# Fri3D_2020_Power.net
KiCad netlist of a schematic drawn in Altium Designer
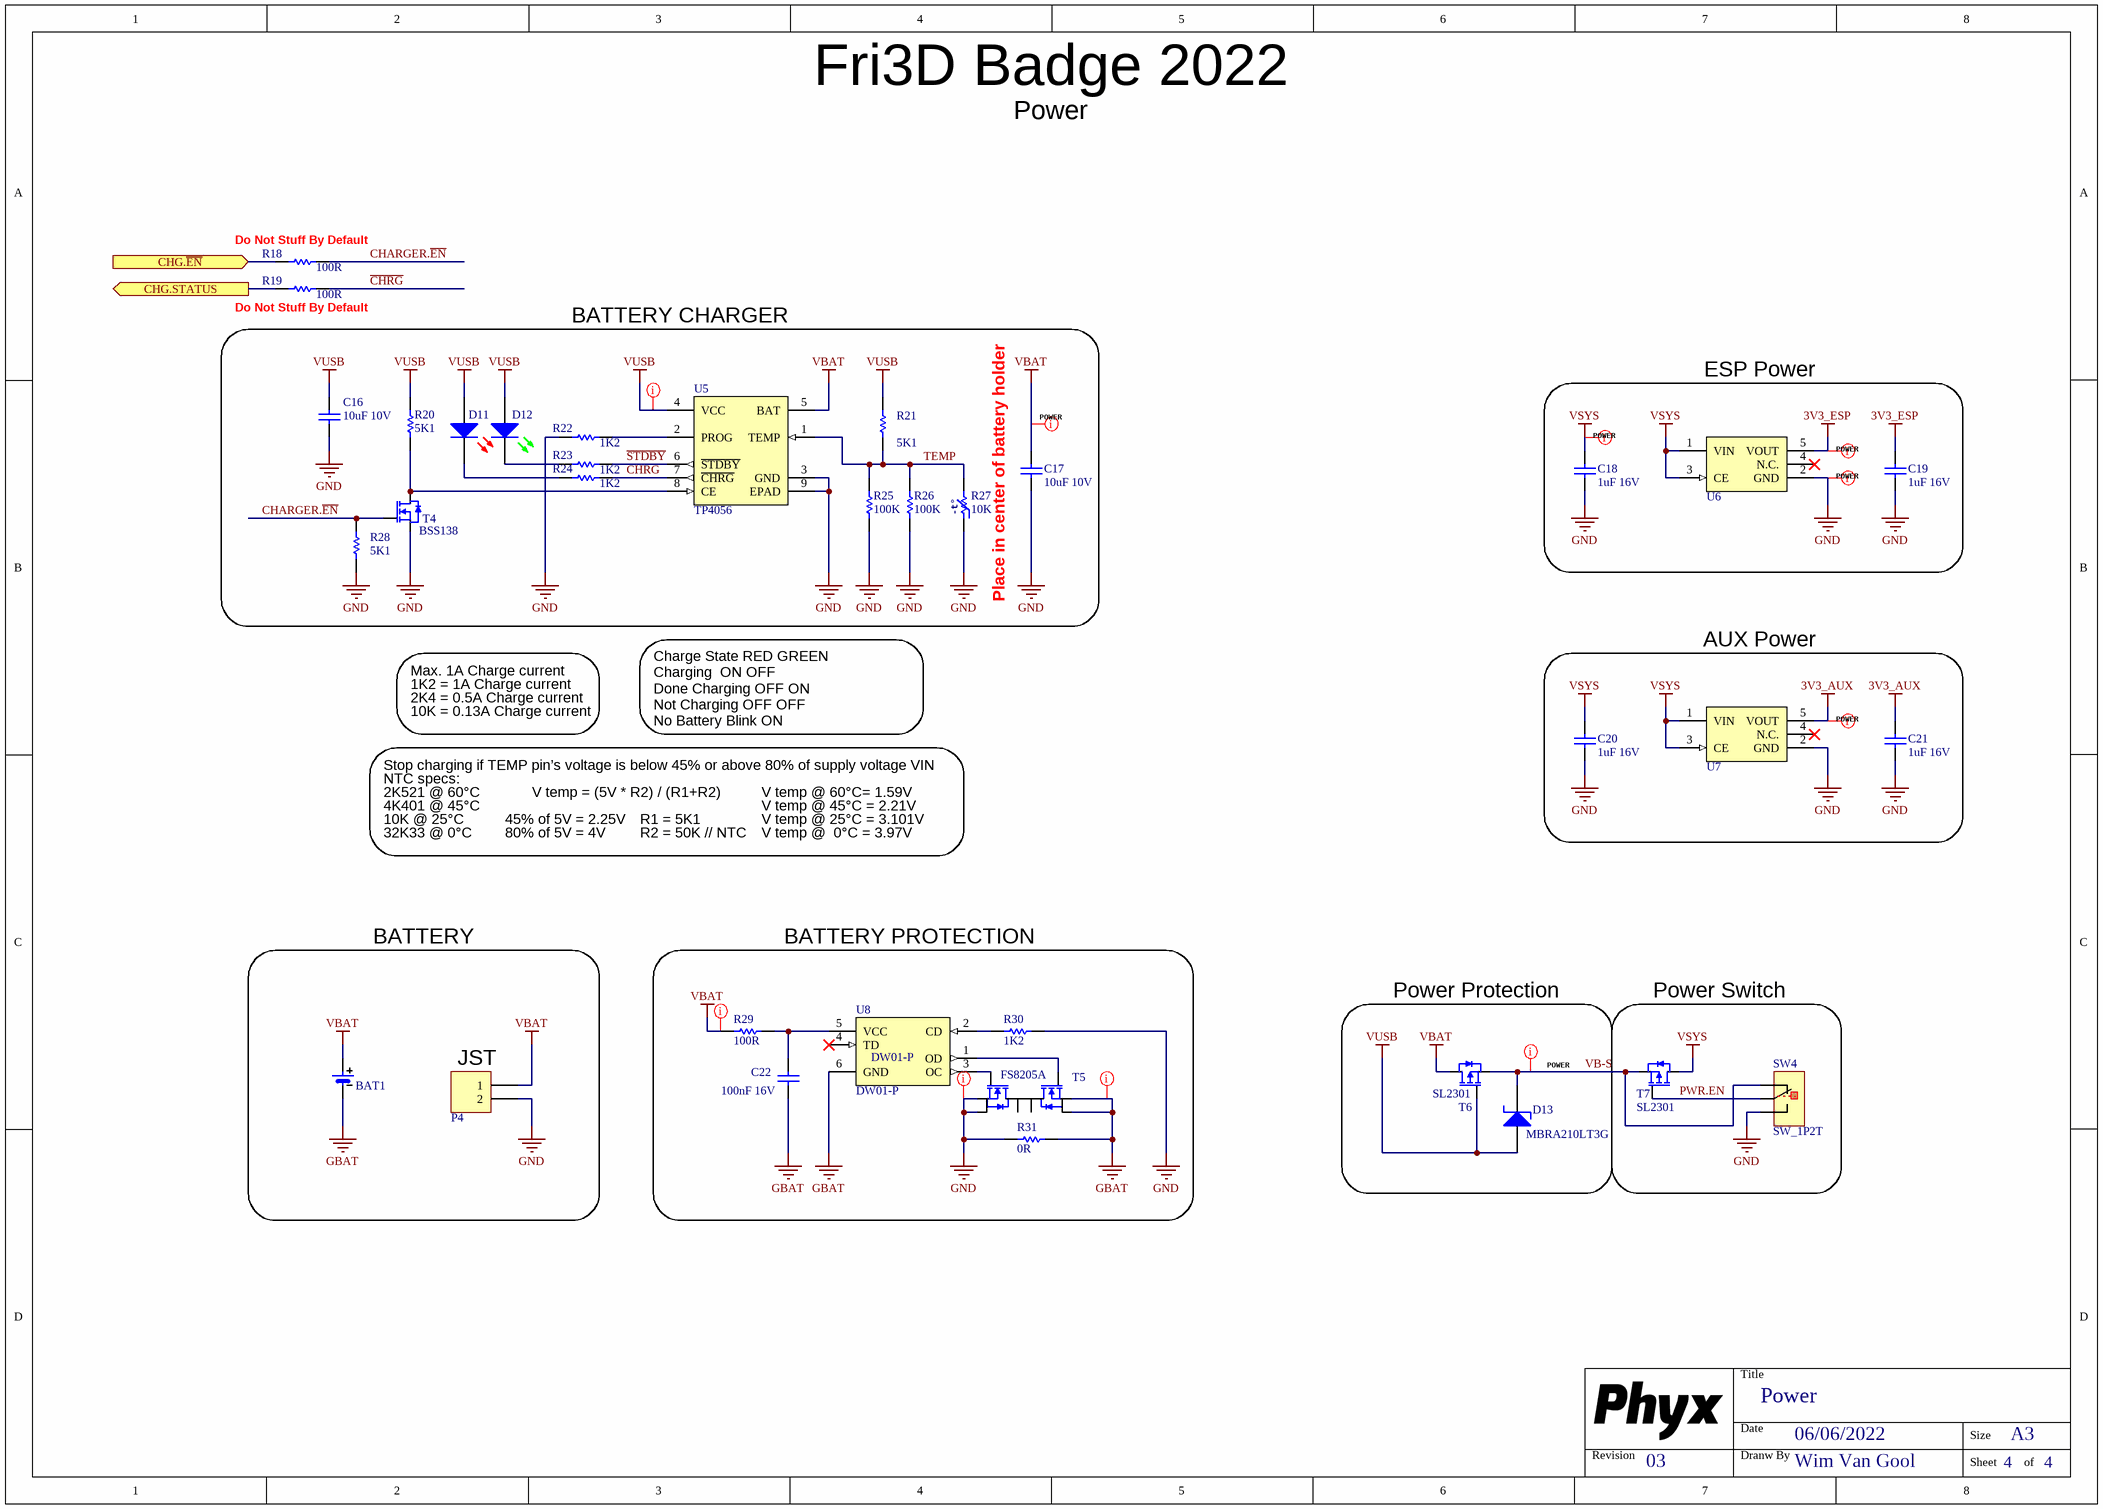
[diagram p0: Fri3D_2020_Power.SchDoc]

(export (version "E")
  (design (tool "Eeschema 10.0.6"))
  (components
    (comp (ref "BAT1")
      (value "18650 Battery holder with spring")
      (footprint "BAT_18650_SPRING")
      (description "=Description")
      (libsource (lib "Phyx_Components") (part "BAT_2"))
    )
    (comp (ref "C16")
      (value "10uF 10V")
      (footprint "C0805_N")
      (description "Capacitor Ceramic")
      (fields (field (name "Comment") "CAP_CERAMIC"))
      (libsource (lib "Phyx_Components") (part "CAP_CERAMIC"))
    )
    (comp (ref "C17")
      (value "10uF 10V")
      (footprint "C0805_N")
      (description "Capacitor Ceramic")
      (fields (field (name "Comment") "CAP_CERAMIC"))
      (libsource (lib "Phyx_Components") (part "CAP_CERAMIC"))
    )
    (comp (ref "C18")
      (value "1uF 16V")
      (footprint "C0603_N")
      (description "Capacitor Ceramic")
      (fields (field (name "Comment") "CAP_CERAMIC"))
      (libsource (lib "Phyx_Components") (part "CAP_CERAMIC"))
    )
    (comp (ref "C19")
      (value "1uF 16V")
      (footprint "C0603_N")
      (description "Capacitor Ceramic")
      (fields (field (name "Comment") "CAP_CERAMIC"))
      (libsource (lib "Phyx_Components") (part "CAP_CERAMIC"))
    )
    (comp (ref "C20")
      (value "1uF 16V")
      (footprint "C0603_N")
      (description "Capacitor Ceramic")
      (fields (field (name "Comment") "CAP_CERAMIC"))
      (libsource (lib "Phyx_Components") (part "CAP_CERAMIC"))
    )
    (comp (ref "C21")
      (value "1uF 16V")
      (footprint "C0603_N")
      (description "Capacitor Ceramic")
      (fields (field (name "Comment") "CAP_CERAMIC"))
      (libsource (lib "Phyx_Components") (part "CAP_CERAMIC"))
    )
    (comp (ref "C22")
      (value "100nF 16V")
      (footprint "C0603_N")
      (description "Capacitor Ceramic")
      (libsource (lib "Phyx_Components") (part "CAP_CERAMIC"))
    )
    (comp (ref "D11")
      (value "Default 0805 Red LED")
      (footprint "LED_0805_RD")
      (description "=Description")
      (libsource (lib "Phyx_Components") (part "LED_RED"))
    )
    (comp (ref "D12")
      (value "Default 0805 Green LED")
      (footprint "LED_0805_GR")
      (description "=Description")
      (libsource (lib "Phyx_Components") (part "LED_GREEN"))
    )
    (comp (ref "D13")
      (value "MBRA210LT3G")
      (footprint "SMA_AC")
      (description "=Description")
      (libsource (lib "Phyx_Components") (part "Schottky_AC"))
    )
    (comp (ref "P4")
      (value "Header 2.0mm Shrouded 2")
      (footprint "WE_620102131822")
      (libsource (lib "Phyx_Components") (part "Header 2"))
    )
    (comp (ref "R18")
      (value "100R")
      (footprint "R0603_N")
      (fields (field (name "Comment") "RESISTOR"))
      (libsource (lib "Phyx_Components") (part "RESISTOR"))
    )
    (comp (ref "R19")
      (value "100R")
      (footprint "R0603_N")
      (fields (field (name "Comment") "RESISTOR"))
      (libsource (lib "Phyx_Components") (part "RESISTOR"))
    )
    (comp (ref "R20")
      (value "5K1")
      (footprint "R0603_N")
      (fields (field (name "Comment") "RESISTOR"))
      (libsource (lib "Phyx_Components") (part "RESISTOR"))
    )
    (comp (ref "R21")
      (value "5K1")
      (footprint "R0603_N")
      (fields (field (name "Comment") "RESISTOR"))
      (libsource (lib "Phyx_Components") (part "RESISTOR"))
    )
    (comp (ref "R22")
      (value "1K2")
      (footprint "R0603_N")
      (fields (field (name "Comment") "RESISTOR"))
      (libsource (lib "Phyx_Components") (part "RESISTOR"))
    )
    (comp (ref "R23")
      (value "1K2")
      (footprint "R0603_N")
      (fields (field (name "Comment") "RESISTOR"))
      (libsource (lib "Phyx_Components") (part "RESISTOR"))
    )
    (comp (ref "R24")
      (value "1K2")
      (footprint "R0603_N")
      (fields (field (name "Comment") "RESISTOR"))
      (libsource (lib "Phyx_Components") (part "RESISTOR"))
    )
    (comp (ref "R25")
      (value "100K")
      (footprint "R0603_N")
      (fields (field (name "Comment") "RESISTOR"))
      (libsource (lib "Phyx_Components") (part "RESISTOR"))
    )
    (comp (ref "R26")
      (value "100K")
      (footprint "R0603_N")
      (fields (field (name "Comment") "RESISTOR"))
      (libsource (lib "Phyx_Components") (part "RESISTOR"))
    )
    (comp (ref "R27")
      (value "10K")
      (footprint "R0402")
      (fields (field (name "Comment") "NTC"))
      (libsource (lib "Phyx_Components") (part "RESISTOR_NTC"))
    )
    (comp (ref "R28")
      (value "5K1")
      (footprint "R0603_N")
      (fields (field (name "Comment") "RESISTOR"))
      (libsource (lib "Phyx_Components") (part "RESISTOR"))
    )
    (comp (ref "R29")
      (value "100R")
      (footprint "R0603_N")
      (fields (field (name "Comment") "RESISTOR"))
      (libsource (lib "Phyx_Components") (part "RESISTOR"))
    )
    (comp (ref "R30")
      (value "1K2")
      (footprint "R0603_N")
      (fields (field (name "Comment") "RESISTOR"))
      (libsource (lib "Phyx_Components") (part "RESISTOR"))
    )
    (comp (ref "R31")
      (value "0R")
      (footprint "R0603_N")
      (libsource (lib "Phyx_Components") (part "RESISTOR"))
    )
    (comp (ref "SW4")
      (value "SW_1P2T")
      (footprint "WE_450404015514")
      (libsource (lib "Phyx_Components") (part "SW_1P2T"))
    )
    (comp (ref "T4")
      (value "BSS138")
      (footprint "SOT23-3")
      (fields (field (name "Comment") "0.2A N-Ch MOSFET Vgs 3.2"))
      (libsource (lib "Phyx_Components") (part "N_MOSFET_GSD"))
    )
    (comp (ref "T5")
      (value "FS8205A")
      (footprint "TSSOP_8_65P")
      (description "=Description")
      (fields (field (name "Comment") "Dual N-Ch MOSFET Common Drain"))
      (libsource (lib "Phyx_Components") (part "N_MOSFET_FS8205A"))
    )
    (comp (ref "T6")
      (value "SL2301")
      (footprint "SOT23-3")
      (description "=Description")
      (fields (field (name "Comment") "-2.3A -20V P-Ch MOSFET Vgs -1V"))
      (libsource (lib "Phyx_Components") (part "P_MOSFET_GSD"))
    )
    (comp (ref "T7")
      (value "SL2301")
      (footprint "SOT23-3")
      (description "=Description")
      (fields (field (name "Comment") "-2.3A -20V P-Ch MOSFET Vgs -1V"))
      (libsource (lib "Phyx_Components") (part "P_MOSFET_GSD"))
    )
    (comp (ref "U5")
      (value "TP4056")
      (footprint "SOIC_N_8_TH")
      (description "=Description")
      (fields (field (name "Comment") "Single Cell LiIon charger max 1A"))
      (libsource (lib "Phyx_Components") (part "TP4056"))
    )
    (comp (ref "U6")
      (value "3V3 LDO 700mA 50mV")
      (footprint "SOT23-5")
      (description "=Designator")
      (libsource (lib "Phyx_Components") (part "XC6210_SOT"))
    )
    (comp (ref "U7")
      (value "3V3 LDO 700mA 50mV")
      (footprint "SOT23-5")
      (description "=Designator")
      (libsource (lib "Phyx_Components") (part "XC6210_SOT"))
    )
    (comp (ref "U8")
      (value "DW01-P")
      (footprint "SOT23-6")
      (description "=Description")
      (fields (field (name "Comment") "DW01-P single cell lithium protection"))
      (libsource (lib "Phyx_Components") (part "DW01-P"))
    )
  )
  (nets
    (net (code "1") (name "/CHARGER.~{EN}") (class "Default")
      (node (ref "R18") (pin "2") (pinfunction "2_2") (pintype "passive"))
      (node (ref "R28") (pin "1") (pinfunction "1_1") (pintype "passive"))
      (node (ref "T4") (pin "1") (pinfunction "G_1") (pintype "passive"))
    )
    (net (code "2") (name "/CHG.STATUS") (class "Default")
      (node (ref "R19") (pin "1") (pinfunction "1_1") (pintype "passive"))
    )
    (net (code "3") (name "/CHG.~{EN}") (class "Default")
      (node (ref "R18") (pin "1") (pinfunction "1_1") (pintype "passive"))
    )
    (net (code "4") (name "/PWR.EN") (class "Default")
      (node (ref "SW4") (pin "2") (pinfunction "2_2") (pintype "passive"))
      (node (ref "T7") (pin "1") (pinfunction "G_1") (pintype "passive"))
    )
    (net (code "5") (name "/TEMP") (class "Default")
      (node (ref "R21") (pin "2") (pinfunction "2_2") (pintype "passive"))
      (node (ref "R25") (pin "1") (pinfunction "1_1") (pintype "passive"))
      (node (ref "R26") (pin "1") (pinfunction "1_1") (pintype "passive"))
      (node (ref "R27") (pin "1") (pinfunction "1_1") (pintype "passive"))
      (node (ref "U5") (pin "1") (pinfunction "TEMP_1") (pintype "input"))
    )
    (net (code "6") (name "/VB-S") (class "Default")
      (node (ref "D13") (pin "C") (pinfunction "C_C") (pintype "passive"))
      (node (ref "SW4") (pin "1") (pinfunction "1_1") (pintype "passive"))
      (node (ref "T6") (pin "2") (pinfunction "S_2") (pintype "passive"))
      (node (ref "T7") (pin "2") (pinfunction "S_2") (pintype "passive"))
    )
    (net (code "7") (name "/~{CHRG}") (class "Default")
      (node (ref "R19") (pin "2") (pinfunction "2_2") (pintype "passive"))
      (node (ref "R24") (pin "2") (pinfunction "2_2") (pintype "passive"))
      (node (ref "U5") (pin "7") (pinfunction "~{CHRG}_7") (pintype "output"))
    )
    (net (code "8") (name "/~{STDBY}") (class "Default")
      (node (ref "R23") (pin "2") (pinfunction "2_2") (pintype "passive"))
      (node (ref "U5") (pin "6") (pinfunction "~{STDBY}_6") (pintype "output"))
    )
    (net (code "9") (name "3V3_AUX") (class "Default")
      (node (ref "C21") (pin "1") (pinfunction "1_1") (pintype "passive"))
      (node (ref "U7") (pin "5") (pinfunction "VOUT_5") (pintype "power_in"))
    )
    (net (code "10") (name "3V3_ESP") (class "Default")
      (node (ref "C19") (pin "1") (pinfunction "1_1") (pintype "passive"))
      (node (ref "U6") (pin "5") (pinfunction "VOUT_5") (pintype "power_in"))
    )
    (net (code "11") (name "GBAT") (class "Default")
      (node (ref "BAT1") (pin "2") (pinfunction "2_2") (pintype "passive"))
      (node (ref "C22") (pin "2") (pinfunction "2_2") (pintype "passive"))
      (node (ref "R31") (pin "1") (pinfunction "1_1") (pintype "passive"))
      (node (ref "T5") (pin "2") (pinfunction "S1_2") (pintype "passive"))
      (node (ref "T5") (pin "3") (pinfunction "S1_3") (pintype "passive"))
      (node (ref "U8") (pin "6") (pinfunction "GND_6") (pintype "power_in"))
    )
    (net (code "12") (name "GND") (class "Default")
      (node (ref "C16") (pin "2") (pinfunction "2_2") (pintype "passive"))
      (node (ref "C17") (pin "2") (pinfunction "2_2") (pintype "passive"))
      (node (ref "C18") (pin "2") (pinfunction "2_2") (pintype "passive"))
      (node (ref "C19") (pin "2") (pinfunction "2_2") (pintype "passive"))
      (node (ref "C20") (pin "2") (pinfunction "2_2") (pintype "passive"))
      (node (ref "C21") (pin "2") (pinfunction "2_2") (pintype "passive"))
      (node (ref "P4") (pin "2") (pinfunction "2_2") (pintype "passive"))
      (node (ref "R22") (pin "2") (pinfunction "2_2") (pintype "passive"))
      (node (ref "R25") (pin "2") (pinfunction "2_2") (pintype "passive"))
      (node (ref "R26") (pin "2") (pinfunction "2_2") (pintype "passive"))
      (node (ref "R27") (pin "2") (pinfunction "2_2") (pintype "passive"))
      (node (ref "R28") (pin "2") (pinfunction "2_2") (pintype "passive"))
      (node (ref "R30") (pin "2") (pinfunction "2_2") (pintype "passive"))
      (node (ref "R31") (pin "2") (pinfunction "2_2") (pintype "passive"))
      (node (ref "SW4") (pin "3") (pinfunction "3_3") (pintype "passive"))
      (node (ref "T4") (pin "2") (pinfunction "S_2") (pintype "passive"))
      (node (ref "T5") (pin "6") (pinfunction "S2_6") (pintype "passive"))
      (node (ref "T5") (pin "7") (pinfunction "S2_7") (pintype "passive"))
      (node (ref "U5") (pin "3") (pinfunction "GND_3") (pintype "power_in"))
      (node (ref "U5") (pin "9") (pinfunction "EPAD_9") (pintype "power_in"))
      (node (ref "U6") (pin "2") (pinfunction "GND_2") (pintype "power_in"))
      (node (ref "U7") (pin "2") (pinfunction "GND_2") (pintype "power_in"))
    )
    (net (code "13") (name "Net-(D11-K)") (class "Default")
      (node (ref "D11") (pin "2") (pinfunction "K_2") (pintype "passive"))
      (node (ref "R24") (pin "1") (pinfunction "1_1") (pintype "passive"))
    )
    (net (code "14") (name "Net-(D12-K)") (class "Default")
      (node (ref "D12") (pin "2") (pinfunction "K_2") (pintype "passive"))
      (node (ref "R23") (pin "1") (pinfunction "1_1") (pintype "passive"))
    )
    (net (code "15") (name "Net-(T4-D)") (class "Default")
      (node (ref "R20") (pin "2") (pinfunction "2_2") (pintype "passive"))
      (node (ref "T4") (pin "3") (pinfunction "D_3") (pintype "passive"))
      (node (ref "U5") (pin "8") (pinfunction "CE_8") (pintype "input"))
    )
    (net (code "16") (name "Net-(T5-G1)") (class "Default")
      (node (ref "T5") (pin "4") (pinfunction "G1_4") (pintype "passive"))
      (node (ref "U8") (pin "1") (pinfunction "OD_1") (pintype "output"))
    )
    (net (code "17") (name "Net-(T5-G2)") (class "Default")
      (node (ref "T5") (pin "5") (pinfunction "G2_5") (pintype "passive"))
      (node (ref "U8") (pin "3") (pinfunction "OC_3") (pintype "output"))
    )
    (net (code "18") (name "Net-(U5-PROG)") (class "Default")
      (node (ref "R22") (pin "1") (pinfunction "1_1") (pintype "passive"))
      (node (ref "U5") (pin "2") (pinfunction "PROG_2") (pintype "passive"))
    )
    (net (code "19") (name "Net-(U8-CD)") (class "Default")
      (node (ref "R30") (pin "1") (pinfunction "1_1") (pintype "passive"))
      (node (ref "U8") (pin "2") (pinfunction "CD_2") (pintype "input"))
    )
    (net (code "20") (name "Net-(U8-VCC)") (class "Default")
      (node (ref "C22") (pin "1") (pinfunction "1_1") (pintype "passive"))
      (node (ref "R29") (pin "2") (pinfunction "2_2") (pintype "passive"))
      (node (ref "U8") (pin "5") (pinfunction "VCC_5") (pintype "power_in"))
    )
    (net (code "21") (name "VBAT") (class "Default")
      (node (ref "BAT1") (pin "1") (pinfunction "1_1") (pintype "passive"))
      (node (ref "C17") (pin "1") (pinfunction "1_1") (pintype "passive"))
      (node (ref "P4") (pin "1") (pinfunction "1_1") (pintype "passive"))
      (node (ref "R29") (pin "1") (pinfunction "1_1") (pintype "passive"))
      (node (ref "T6") (pin "3") (pinfunction "D_3") (pintype "passive"))
      (node (ref "U5") (pin "5") (pinfunction "BAT_5") (pintype "power_in"))
    )
    (net (code "22") (name "VSYS") (class "Default")
      (node (ref "C18") (pin "1") (pinfunction "1_1") (pintype "passive"))
      (node (ref "C20") (pin "1") (pinfunction "1_1") (pintype "passive"))
      (node (ref "T7") (pin "3") (pinfunction "D_3") (pintype "passive"))
      (node (ref "U6") (pin "1") (pinfunction "VIN_1") (pintype "power_in"))
      (node (ref "U6") (pin "3") (pinfunction "CE_3") (pintype "input"))
      (node (ref "U7") (pin "1") (pinfunction "VIN_1") (pintype "power_in"))
      (node (ref "U7") (pin "3") (pinfunction "CE_3") (pintype "input"))
    )
    (net (code "23") (name "VUSB") (class "Default")
      (node (ref "C16") (pin "1") (pinfunction "1_1") (pintype "passive"))
      (node (ref "D11") (pin "1") (pinfunction "A_1") (pintype "passive"))
      (node (ref "D12") (pin "1") (pinfunction "A_1") (pintype "passive"))
      (node (ref "D13") (pin "A") (pinfunction "A_A") (pintype "passive"))
      (node (ref "R20") (pin "1") (pinfunction "1_1") (pintype "passive"))
      (node (ref "R21") (pin "1") (pinfunction "1_1") (pintype "passive"))
      (node (ref "T6") (pin "1") (pinfunction "G_1") (pintype "passive"))
      (node (ref "U5") (pin "4") (pinfunction "VCC_4") (pintype "power_in"))
    )
    (net (code "24") (name "unconnected-(T5-D1-Pad1)") (class "Default")
      (node (ref "T5") (pin "1") (pinfunction "D1_1") (pintype "passive"))
    )
    (net (code "25") (name "unconnected-(T5-D2-Pad8)") (class "Default")
      (node (ref "T5") (pin "8") (pinfunction "D2_8") (pintype "passive"))
    )
    (net (code "26") (name "unconnected-(U6-N.C.-Pad4)") (class "Default")
      (node (ref "U6") (pin "4") (pinfunction "N.C._4") (pintype "passive+no_connect"))
    )
    (net (code "27") (name "unconnected-(U7-N.C.-Pad4)") (class "Default")
      (node (ref "U7") (pin "4") (pinfunction "N.C._4") (pintype "passive+no_connect"))
    )
    (net (code "28") (name "unconnected-(U8-TD-Pad4)") (class "Default")
      (node (ref "U8") (pin "4") (pinfunction "TD_4") (pintype "input+no_connect"))
    )
  )
)
